# STM32.net
KiCad netlist of a schematic drawn in Altium Designer
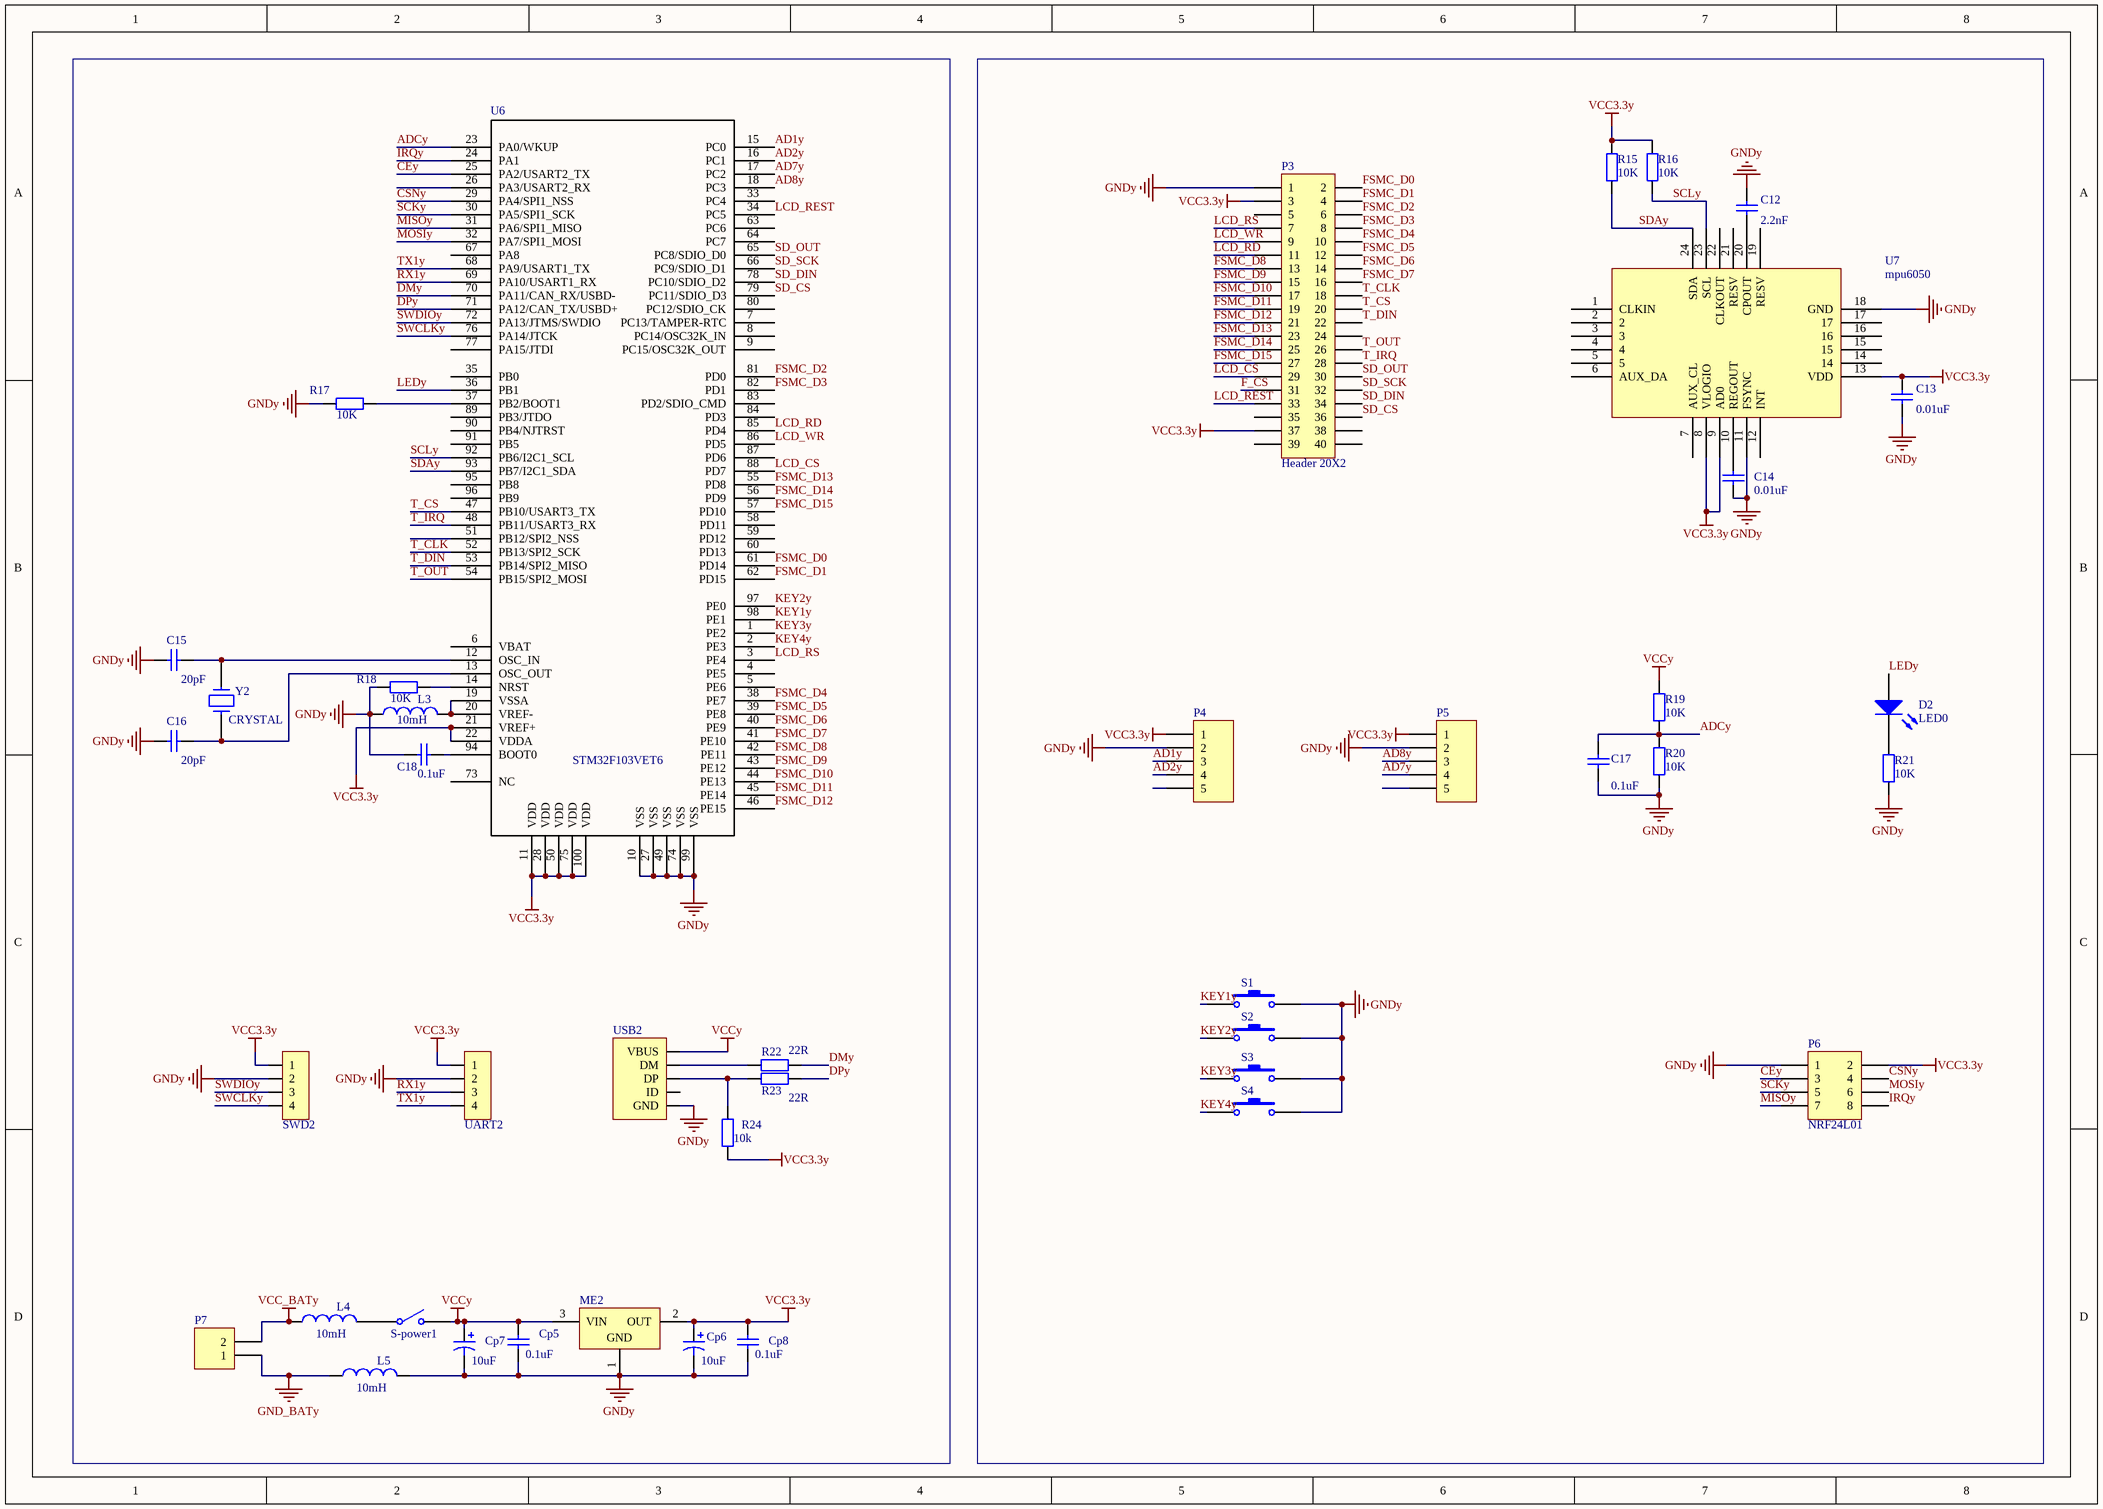
[diagram p0: STM32遥控.SchDoc]

(export (version "E")
  (design (tool "Eeschema 10.0.6"))
  (components
    (comp (ref "C12")
      (value "2.2nF")
      (footprint "0805s")
      (description "Capacitor")
      (fields (field (name "Comment") "Cap") (field (name "PUBLISHER") "Altium Limited"))
      (libsource (lib "Miscellaneous Devices") (part "Cap"))
    )
    (comp (ref "C13")
      (value "0.01uF")
      (footprint "0805s")
      (description "Capacitor")
      (fields (field (name "Comment") "Cap") (field (name "PUBLISHER") "Altium Limited"))
      (libsource (lib "Miscellaneous Devices") (part "Cap"))
    )
    (comp (ref "C14")
      (value "0.01uF")
      (footprint "0805s")
      (description "Capacitor")
      (fields (field (name "Comment") "Cap") (field (name "PUBLISHER") "Altium Limited"))
      (libsource (lib "Miscellaneous Devices") (part "Cap"))
    )
    (comp (ref "C15")
      (value "20pF")
      (footprint "0805s")
      (description "Capacitor")
      (fields (field (name "Comment") "Cap") (field (name "PUBLISHER") "Altium Limited"))
      (libsource (lib "Miscellaneous Devices") (part "Cap"))
    )
    (comp (ref "C16")
      (value "20pF")
      (footprint "0805s")
      (description "Capacitor")
      (fields (field (name "Comment") "Cap") (field (name "PUBLISHER") "Altium Limited"))
      (libsource (lib "Miscellaneous Devices") (part "Cap"))
    )
    (comp (ref "C17")
      (value "0.1uF")
      (footprint "0805s")
      (description "Capacitor")
      (fields (field (name "Comment") "Cap") (field (name "PUBLISHER") "Altium Limited"))
      (libsource (lib "Miscellaneous Devices") (part "Cap"))
    )
    (comp (ref "C18")
      (value "0.1uF")
      (footprint "0805s")
      (description "Capacitor")
      (fields (field (name "Comment") "Cap") (field (name "PUBLISHER") "Altium Limited"))
      (libsource (lib "Miscellaneous Devices") (part "Cap"))
    )
    (comp (ref "Cp5")
      (value "0.1uF")
      (footprint "0805s")
      (description "Capacitor")
      (fields (field (name "Comment") "Cap") (field (name "PUBLISHER") "Altium Limited"))
      (libsource (lib "Miscellaneous Devices") (part "Cap"))
    )
    (comp (ref "Cp6")
      (value "10uF")
      (footprint "3216")
      (description "Polarized Capacitor (Radial)")
      (fields (field (name "Comment") "Cap Pol1") (field (name "PUBLISHER") "Altium Limited"))
      (libsource (lib "Miscellaneous Devices") (part "Cap Pol1"))
    )
    (comp (ref "Cp7")
      (value "10uF")
      (footprint "3216")
      (description "Polarized Capacitor (Radial)")
      (fields (field (name "Comment") "Cap Pol1") (field (name "PUBLISHER") "Altium Limited"))
      (libsource (lib "Miscellaneous Devices") (part "Cap Pol1"))
    )
    (comp (ref "Cp8")
      (value "0.1uF")
      (footprint "0805s")
      (description "Capacitor")
      (fields (field (name "Comment") "Cap") (field (name "PUBLISHER") "Altium Limited"))
      (libsource (lib "Miscellaneous Devices") (part "Cap"))
    )
    (comp (ref "D2")
      (value "LED0")
      (footprint "0805s")
      (description "Typical INFRARED GaAs LED")
      (fields (field (name "PUBLISHER") "Altium Limited"))
      (libsource (lib "Miscellaneous Devices") (part "LED0"))
    )
    (comp (ref "L3")
      (value "10mH")
      (footprint "0805s")
      (description "Inductor")
      (fields (field (name "PUBLISHER") "Altium Limited"))
      (libsource (lib "Miscellaneous Devices") (part "Inductor"))
    )
    (comp (ref "L4")
      (value "10mH")
      (footprint "0805s")
      (description "Inductor")
      (fields (field (name "PUBLISHER") "Altium Limited"))
      (libsource (lib "Miscellaneous Devices") (part "Inductor"))
    )
    (comp (ref "L5")
      (value "10mH")
      (footprint "0805s")
      (description "Inductor")
      (fields (field (name "PUBLISHER") "Altium Limited"))
      (libsource (lib "Miscellaneous Devices") (part "Inductor"))
    )
    (comp (ref "ME2")
      (value "Volt Reg")
      (footprint "SOT-23")
      (description "Voltage Regulator")
      (fields (field (name "PUBLISHER") "Altium Limited"))
      (libsource (lib "Miscellaneous Devices") (part "Volt Reg"))
    )
    (comp (ref "P3")
      (value "Header 20X2")
      (footprint "HDR2X20")
      (description "Header, 20-Pin, Dual row")
      (fields (field (name "PUBLISHER") "Altium Limited"))
      (libsource (lib "Miscellaneous Connectors") (part "Header 20X2"))
    )
    (comp (ref "P4")
      (value "Header 5")
      (footprint "yaogan")
      (description "Header, 5-Pin")
      (fields (field (name "PUBLISHER") "Altium Limited"))
      (libsource (lib "Miscellaneous Connectors") (part "Header 5"))
    )
    (comp (ref "P5")
      (value "Header 5")
      (footprint "yaogan")
      (description "Header, 5-Pin")
      (fields (field (name "PUBLISHER") "Altium Limited"))
      (libsource (lib "Miscellaneous Connectors") (part "Header 5"))
    )
    (comp (ref "P6")
      (value "NRF24L01")
      (footprint "HDR2X4")
      (description "Header, 4-Pin, Dual row")
      (fields (field (name "PUBLISHER") "Altium Limited"))
      (libsource (lib "Miscellaneous Connectors") (part "MHDR2X4"))
    )
    (comp (ref "P7")
      (value "Header 2")
      (footprint "SIP2")
      (description "Header, 2-Pin")
      (fields (field (name "PUBLISHER") "Altium Limited"))
      (libsource (lib "Miscellaneous Connectors") (part "Header 2"))
    )
    (comp (ref "R15")
      (value "10K")
      (footprint "0805s")
      (description "Resistor")
      (fields (field (name "Comment") "Res2") (field (name "PUBLISHER") "Altium Limited"))
      (libsource (lib "Miscellaneous Devices") (part "Res2"))
    )
    (comp (ref "R16")
      (value "10K")
      (footprint "0805s")
      (description "Resistor")
      (fields (field (name "Comment") "Res2") (field (name "PUBLISHER") "Altium Limited"))
      (libsource (lib "Miscellaneous Devices") (part "Res2"))
    )
    (comp (ref "R17")
      (value "10K")
      (footprint "0805s")
      (description "Resistor")
      (fields (field (name "Comment") "Res2") (field (name "PUBLISHER") "Altium Limited"))
      (libsource (lib "") (part "Res2_1"))
    )
    (comp (ref "R18")
      (value "10K")
      (footprint "0805s")
      (description "Resistor")
      (fields (field (name "Comment") "Res2") (field (name "PUBLISHER") "Altium Limited"))
      (libsource (lib "") (part "Res2_1"))
    )
    (comp (ref "R19")
      (value "10K")
      (footprint "0805s")
      (description "Resistor")
      (fields (field (name "Comment") "Res2") (field (name "PUBLISHER") "Altium Limited"))
      (libsource (lib "Miscellaneous Devices") (part "Res2"))
    )
    (comp (ref "R20")
      (value "10K")
      (footprint "0805s")
      (description "Resistor")
      (fields (field (name "Comment") "Res2") (field (name "PUBLISHER") "Altium Limited"))
      (libsource (lib "Miscellaneous Devices") (part "Res2"))
    )
    (comp (ref "R21")
      (value "10K")
      (footprint "0805s")
      (description "Resistor")
      (fields (field (name "Comment") "Res2") (field (name "PUBLISHER") "Altium Limited"))
      (libsource (lib "Miscellaneous Devices") (part "Res2"))
    )
    (comp (ref "R22")
      (value "22R")
      (footprint "0805s")
      (description "Resistor")
      (fields (field (name "Comment") "Res_0603"))
      (libsource (lib "SCH_Passive") (part "Res_0603"))
    )
    (comp (ref "R23")
      (value "22R")
      (footprint "0805s")
      (description "Resistor")
      (fields (field (name "Comment") "Res_0603"))
      (libsource (lib "SCH_Passive") (part "Res_0603"))
    )
    (comp (ref "R24")
      (value "10k")
      (footprint "常用元件封装:0805s")
      (description "Resistor")
      (fields (field (name "Comment") "Res_0603"))
      (libsource (lib "") (part "Res_0603_1"))
    )
    (comp (ref "S-power1")
      (value "SW-SPST")
      (footprint "SIP3")
      (description "Single-Pole, Single-Throw Switch")
      (fields (field (name "PUBLISHER") "Altium Limited"))
      (libsource (lib "Miscellaneous Devices") (part "SW-SPST"))
    )
    (comp (ref "S1")
      (value "SW-PB")
      (footprint "按键")
      (description "Switch")
      (fields (field (name "PUBLISHER") "Altium Limited"))
      (libsource (lib "Miscellaneous Devices") (part "SW-PB"))
    )
    (comp (ref "S2")
      (value "SW-PB")
      (footprint "按键")
      (description "Switch")
      (fields (field (name "PUBLISHER") "Altium Limited"))
      (libsource (lib "Miscellaneous Devices") (part "SW-PB"))
    )
    (comp (ref "S3")
      (value "SW-PB")
      (footprint "按键")
      (description "Switch")
      (fields (field (name "PUBLISHER") "Altium Limited"))
      (libsource (lib "Miscellaneous Devices") (part "SW-PB"))
    )
    (comp (ref "S4")
      (value "SW-PB")
      (footprint "按键")
      (description "Switch")
      (fields (field (name "PUBLISHER") "Altium Limited"))
      (libsource (lib "Miscellaneous Devices") (part "SW-PB"))
    )
    (comp (ref "SWD2")
      (value "HDR1X4_180_2.54")
      (footprint "SIP4")
      (description "Header")
      (libsource (lib "SCH_Connector") (part "HDR1X4_180_2.54"))
    )
    (comp (ref "U6")
      (value "STM32F103VET6")
      (footprint "LQFP100_N")
      (libsource (lib "Schlib1") (part "STM32F103VET6"))
    )
    (comp (ref "U7") (value "mpu6050") (footprint "MPU6050") (libsource (lib "四轴") (part "mpu6050")))
    (comp (ref "UART2")
      (value "HDR1X4_180_2.54")
      (footprint "SIP4")
      (description "Header")
      (libsource (lib "SCH_Connector") (part "HDR1X4_180_2.54"))
    )
    (comp (ref "USB2")
      (value "USB_Micro")
      (footprint "MICRO-USB")
      (description "USB")
      (libsource (lib "SCH_USB") (part "USB_Micro"))
    )
    (comp (ref "Y2")
      (value "CRYSTAL")
      (footprint "SIP2")
      (description "Crystal")
      (libsource (lib "杂元件库") (part "CRYSTAL"))
    )
  )
  (nets
    (net (code "1") (name "/AD1y") (class "Default")
      (node (ref "P4") (pin "3") (pinfunction "3_3") (pintype "passive"))
      (node (ref "U6") (pin "15") (pinfunction "PC0_15") (pintype "passive"))
    )
    (net (code "2") (name "/AD2y") (class "Default")
      (node (ref "P4") (pin "4") (pinfunction "4_4") (pintype "passive"))
      (node (ref "U6") (pin "16") (pinfunction "PC1_16") (pintype "passive"))
    )
    (net (code "3") (name "/AD7y") (class "Default")
      (node (ref "P5") (pin "4") (pinfunction "4_4") (pintype "passive"))
      (node (ref "U6") (pin "17") (pinfunction "PC2_17") (pintype "passive"))
    )
    (net (code "4") (name "/AD8y") (class "Default")
      (node (ref "P5") (pin "3") (pinfunction "3_3") (pintype "passive"))
      (node (ref "U6") (pin "18") (pinfunction "PC3_18") (pintype "passive"))
    )
    (net (code "5") (name "/ADCy") (class "Default")
      (node (ref "C17") (pin "2") (pinfunction "2_2") (pintype "passive"))
      (node (ref "R19") (pin "1") (pinfunction "1_1") (pintype "passive"))
      (node (ref "R20") (pin "2") (pinfunction "2_2") (pintype "passive"))
      (node (ref "U6") (pin "23") (pinfunction "PA0/WKUP_23") (pintype "passive"))
    )
    (net (code "6") (name "/CEy") (class "Default")
      (node (ref "P6") (pin "3") (pinfunction "3_3") (pintype "passive"))
      (node (ref "U6") (pin "25") (pinfunction "PA2/USART2_TX_25") (pintype "passive"))
    )
    (net (code "7") (name "/CSNy") (class "Default")
      (node (ref "P6") (pin "4") (pinfunction "4_4") (pintype "passive"))
      (node (ref "U6") (pin "29") (pinfunction "PA4/SPI1_NSS_29") (pintype "passive"))
    )
    (net (code "8") (name "/DMy") (class "Default")
      (node (ref "R22") (pin "2") (pinfunction "2_2") (pintype "passive"))
      (node (ref "U6") (pin "70") (pinfunction "PA11/CAN_RX/USBD-_70") (pintype "passive"))
    )
    (net (code "9") (name "/DPy") (class "Default")
      (node (ref "R23") (pin "2") (pinfunction "2_2") (pintype "passive"))
      (node (ref "U6") (pin "71") (pinfunction "PA12/CAN_TX/USBD+_71") (pintype "passive"))
    )
    (net (code "10") (name "/FSMC_D0") (class "Default")
      (node (ref "P3") (pin "2") (pinfunction "2_2") (pintype "passive"))
      (node (ref "U6") (pin "61") (pinfunction "PD14_61") (pintype "passive"))
    )
    (net (code "11") (name "/FSMC_D1") (class "Default")
      (node (ref "P3") (pin "4") (pinfunction "4_4") (pintype "passive"))
      (node (ref "U6") (pin "62") (pinfunction "PD15_62") (pintype "passive"))
    )
    (net (code "12") (name "/FSMC_D2") (class "Default")
      (node (ref "P3") (pin "6") (pinfunction "6_6") (pintype "passive"))
      (node (ref "U6") (pin "81") (pinfunction "PD0_81") (pintype "passive"))
    )
    (net (code "13") (name "/FSMC_D3") (class "Default")
      (node (ref "P3") (pin "8") (pinfunction "8_8") (pintype "passive"))
      (node (ref "U6") (pin "82") (pinfunction "PD1_82") (pintype "passive"))
    )
    (net (code "14") (name "/FSMC_D4") (class "Default")
      (node (ref "P3") (pin "10") (pinfunction "10_10") (pintype "passive"))
      (node (ref "U6") (pin "38") (pinfunction "PE7_38") (pintype "passive"))
    )
    (net (code "15") (name "/FSMC_D5") (class "Default")
      (node (ref "P3") (pin "12") (pinfunction "12_12") (pintype "passive"))
      (node (ref "U6") (pin "39") (pinfunction "PE8_39") (pintype "passive"))
    )
    (net (code "16") (name "/FSMC_D6") (class "Default")
      (node (ref "P3") (pin "14") (pinfunction "14_14") (pintype "passive"))
      (node (ref "U6") (pin "40") (pinfunction "PE9_40") (pintype "passive"))
    )
    (net (code "17") (name "/FSMC_D7") (class "Default")
      (node (ref "P3") (pin "16") (pinfunction "16_16") (pintype "passive"))
      (node (ref "U6") (pin "41") (pinfunction "PE10_41") (pintype "passive"))
    )
    (net (code "18") (name "/FSMC_D8") (class "Default")
      (node (ref "P3") (pin "13") (pinfunction "13_13") (pintype "passive"))
      (node (ref "U6") (pin "42") (pinfunction "PE11_42") (pintype "passive"))
    )
    (net (code "19") (name "/FSMC_D9") (class "Default")
      (node (ref "P3") (pin "15") (pinfunction "15_15") (pintype "passive"))
      (node (ref "U6") (pin "43") (pinfunction "PE12_43") (pintype "passive"))
    )
    (net (code "20") (name "/FSMC_D10") (class "Default")
      (node (ref "P3") (pin "17") (pinfunction "17_17") (pintype "passive"))
      (node (ref "U6") (pin "44") (pinfunction "PE13_44") (pintype "passive"))
    )
    (net (code "21") (name "/FSMC_D11") (class "Default")
      (node (ref "P3") (pin "19") (pinfunction "19_19") (pintype "passive"))
      (node (ref "U6") (pin "45") (pinfunction "PE14_45") (pintype "passive"))
    )
    (net (code "22") (name "/FSMC_D12") (class "Default")
      (node (ref "P3") (pin "21") (pinfunction "21_21") (pintype "passive"))
      (node (ref "U6") (pin "46") (pinfunction "PE15_46") (pintype "passive"))
    )
    (net (code "23") (name "/FSMC_D13") (class "Default")
      (node (ref "P3") (pin "23") (pinfunction "23_23") (pintype "passive"))
      (node (ref "U6") (pin "55") (pinfunction "PD8_55") (pintype "passive"))
    )
    (net (code "24") (name "/FSMC_D14") (class "Default")
      (node (ref "P3") (pin "25") (pinfunction "25_25") (pintype "passive"))
      (node (ref "U6") (pin "56") (pinfunction "PD9_56") (pintype "passive"))
    )
    (net (code "25") (name "/FSMC_D15") (class "Default")
      (node (ref "P3") (pin "27") (pinfunction "27_27") (pintype "passive"))
      (node (ref "U6") (pin "57") (pinfunction "PD10_57") (pintype "passive"))
    )
    (net (code "26") (name "/F_CS") (class "Default")
      (node (ref "P3") (pin "31") (pinfunction "31_31") (pintype "passive"))
    )
    (net (code "27") (name "/IRQy") (class "Default")
      (node (ref "P6") (pin "8") (pinfunction "8_8") (pintype "passive"))
      (node (ref "U6") (pin "24") (pinfunction "PA1_24") (pintype "passive"))
    )
    (net (code "28") (name "/KEY1y") (class "Default")
      (node (ref "S1") (pin "1") (pinfunction "1_1") (pintype "passive"))
      (node (ref "U6") (pin "98") (pinfunction "PE1_98") (pintype "passive"))
    )
    (net (code "29") (name "/KEY2y") (class "Default")
      (node (ref "S2") (pin "1") (pinfunction "1_1") (pintype "passive"))
      (node (ref "U6") (pin "97") (pinfunction "PE0_97") (pintype "passive"))
    )
    (net (code "30") (name "/KEY3y") (class "Default")
      (node (ref "S3") (pin "1") (pinfunction "1_1") (pintype "passive"))
      (node (ref "U6") (pin "1") (pinfunction "PE2_1") (pintype "passive"))
    )
    (net (code "31") (name "/KEY4y") (class "Default")
      (node (ref "S4") (pin "1") (pinfunction "1_1") (pintype "passive"))
      (node (ref "U6") (pin "2") (pinfunction "PE3_2") (pintype "passive"))
    )
    (net (code "32") (name "/LCD_CS") (class "Default")
      (node (ref "P3") (pin "29") (pinfunction "29_29") (pintype "passive"))
      (node (ref "U6") (pin "88") (pinfunction "PD7_88") (pintype "passive"))
    )
    (net (code "33") (name "/LCD_RD") (class "Default")
      (node (ref "P3") (pin "11") (pinfunction "11_11") (pintype "passive"))
      (node (ref "U6") (pin "85") (pinfunction "PD4_85") (pintype "passive"))
    )
    (net (code "34") (name "/LCD_REST") (class "Default")
      (node (ref "P3") (pin "33") (pinfunction "33_33") (pintype "passive"))
      (node (ref "U6") (pin "34") (pinfunction "PC5_34") (pintype "passive"))
    )
    (net (code "35") (name "/LCD_RS") (class "Default")
      (node (ref "P3") (pin "7") (pinfunction "7_7") (pintype "passive"))
      (node (ref "U6") (pin "3") (pinfunction "PE4_3") (pintype "passive"))
    )
    (net (code "36") (name "/LCD_WR") (class "Default")
      (node (ref "P3") (pin "9") (pinfunction "9_9") (pintype "passive"))
      (node (ref "U6") (pin "86") (pinfunction "PD5_86") (pintype "passive"))
    )
    (net (code "37") (name "/LEDy") (class "Default")
      (node (ref "D2") (pin "1") (pinfunction "A_1") (pintype "passive"))
      (node (ref "U6") (pin "36") (pinfunction "PB1_36") (pintype "passive"))
    )
    (net (code "38") (name "/MISOy") (class "Default")
      (node (ref "P6") (pin "7") (pinfunction "7_7") (pintype "passive"))
      (node (ref "U6") (pin "31") (pinfunction "PA6/SPI1_MISO_31") (pintype "passive"))
    )
    (net (code "39") (name "/MOSIy") (class "Default")
      (node (ref "P6") (pin "6") (pinfunction "6_6") (pintype "passive"))
      (node (ref "U6") (pin "32") (pinfunction "PA7/SPI1_MOSI_32") (pintype "passive"))
    )
    (net (code "40") (name "/RX1y") (class "Default")
      (node (ref "U6") (pin "69") (pinfunction "PA10/USART1_RX_69") (pintype "passive"))
      (node (ref "UART2") (pin "3") (pinfunction "3_3") (pintype "passive"))
    )
    (net (code "41") (name "/SCKy") (class "Default")
      (node (ref "P6") (pin "5") (pinfunction "5_5") (pintype "passive"))
      (node (ref "U6") (pin "30") (pinfunction "PA5/SPI1_SCK_30") (pintype "passive"))
    )
    (net (code "42") (name "/SCLy") (class "Default")
      (node (ref "R16") (pin "1") (pinfunction "1_1") (pintype "passive"))
      (node (ref "U6") (pin "92") (pinfunction "PB6/I2C1_SCL_92") (pintype "passive"))
      (node (ref "U7") (pin "23") (pinfunction "SCL_23") (pintype "passive"))
    )
    (net (code "43") (name "/SDAy") (class "Default")
      (node (ref "R15") (pin "1") (pinfunction "1_1") (pintype "passive"))
      (node (ref "U6") (pin "93") (pinfunction "PB7/I2C1_SDA_93") (pintype "passive"))
      (node (ref "U7") (pin "24") (pinfunction "SDA_24") (pintype "passive"))
    )
    (net (code "44") (name "/SD_CS") (class "Default")
      (node (ref "P3") (pin "36") (pinfunction "36_36") (pintype "passive"))
      (node (ref "U6") (pin "79") (pinfunction "PC11/SDIO_D3_79") (pintype "passive"))
    )
    (net (code "45") (name "/SD_DIN") (class "Default")
      (node (ref "P3") (pin "34") (pinfunction "34_34") (pintype "passive"))
      (node (ref "U6") (pin "78") (pinfunction "PC10/SDIO_D2_78") (pintype "passive"))
    )
    (net (code "46") (name "/SD_OUT") (class "Default")
      (node (ref "P3") (pin "30") (pinfunction "30_30") (pintype "passive"))
      (node (ref "U6") (pin "65") (pinfunction "PC8/SDIO_D0_65") (pintype "passive"))
    )
    (net (code "47") (name "/SD_SCK") (class "Default")
      (node (ref "P3") (pin "32") (pinfunction "32_32") (pintype "passive"))
      (node (ref "U6") (pin "66") (pinfunction "PC9/SDIO_D1_66") (pintype "passive"))
    )
    (net (code "48") (name "/SWCLKy") (class "Default")
      (node (ref "SWD2") (pin "4") (pinfunction "4_4") (pintype "passive"))
      (node (ref "U6") (pin "76") (pinfunction "PA14/JTCK_76") (pintype "passive"))
    )
    (net (code "49") (name "/SWDIOy") (class "Default")
      (node (ref "SWD2") (pin "3") (pinfunction "3_3") (pintype "passive"))
      (node (ref "U6") (pin "72") (pinfunction "PA13/JTMS/SWDIO_72") (pintype "passive"))
    )
    (net (code "50") (name "/TX1y") (class "Default")
      (node (ref "U6") (pin "68") (pinfunction "PA9/USART1_TX_68") (pintype "passive"))
      (node (ref "UART2") (pin "4") (pinfunction "4_4") (pintype "passive"))
    )
    (net (code "51") (name "/T_CLK") (class "Default")
      (node (ref "P3") (pin "18") (pinfunction "18_18") (pintype "passive"))
      (node (ref "U6") (pin "52") (pinfunction "PB13/SPI2_SCK_52") (pintype "passive"))
    )
    (net (code "52") (name "/T_CS") (class "Default")
      (node (ref "P3") (pin "20") (pinfunction "20_20") (pintype "passive"))
      (node (ref "U6") (pin "47") (pinfunction "PB10/USART3_TX_47") (pintype "passive"))
    )
    (net (code "53") (name "/T_DIN") (class "Default")
      (node (ref "P3") (pin "22") (pinfunction "22_22") (pintype "passive"))
      (node (ref "U6") (pin "53") (pinfunction "PB14/SPI2_MISO_53") (pintype "passive"))
    )
    (net (code "54") (name "/T_IRQ") (class "Default")
      (node (ref "P3") (pin "28") (pinfunction "28_28") (pintype "passive"))
      (node (ref "U6") (pin "48") (pinfunction "PB11/USART3_RX_48") (pintype "passive"))
    )
    (net (code "55") (name "/T_OUT") (class "Default")
      (node (ref "P3") (pin "26") (pinfunction "26_26") (pintype "passive"))
      (node (ref "U6") (pin "54") (pinfunction "PB15/SPI2_MOSI_54") (pintype "passive"))
    )
    (net (code "56") (name "GND_BATy") (class "Default")
      (node (ref "L5") (pin "1") (pinfunction "1_1") (pintype "passive"))
      (node (ref "P7") (pin "1") (pinfunction "1_1") (pintype "passive"))
    )
    (net (code "57") (name "GNDy") (class "Default")
      (node (ref "C12") (pin "2") (pinfunction "2_2") (pintype "passive"))
      (node (ref "C13") (pin "1") (pinfunction "1_1") (pintype "passive"))
      (node (ref "C14") (pin "1") (pinfunction "1_1") (pintype "passive"))
      (node (ref "C15") (pin "1") (pinfunction "1_1") (pintype "passive"))
      (node (ref "C16") (pin "1") (pinfunction "1_1") (pintype "passive"))
      (node (ref "C17") (pin "1") (pinfunction "1_1") (pintype "passive"))
      (node (ref "C18") (pin "1") (pinfunction "1_1") (pintype "passive"))
      (node (ref "Cp5") (pin "1") (pinfunction "1_1") (pintype "passive"))
      (node (ref "Cp6") (pin "2") (pinfunction "2_2") (pintype "passive"))
      (node (ref "Cp7") (pin "2") (pinfunction "2_2") (pintype "passive"))
      (node (ref "Cp8") (pin "1") (pinfunction "1_1") (pintype "passive"))
      (node (ref "L3") (pin "1") (pinfunction "1_1") (pintype "passive"))
      (node (ref "L5") (pin "2") (pinfunction "2_2") (pintype "passive"))
      (node (ref "ME2") (pin "1") (pinfunction "GND_1") (pintype "passive"))
      (node (ref "P3") (pin "1") (pinfunction "1_1") (pintype "passive"))
      (node (ref "P4") (pin "2") (pinfunction "2_2") (pintype "passive"))
      (node (ref "P5") (pin "2") (pinfunction "2_2") (pintype "passive"))
      (node (ref "P6") (pin "1") (pinfunction "1_1") (pintype "passive"))
      (node (ref "R17") (pin "2") (pinfunction "2_2") (pintype "passive"))
      (node (ref "R18") (pin "2") (pinfunction "2_2") (pintype "passive"))
      (node (ref "R20") (pin "1") (pinfunction "1_1") (pintype "passive"))
      (node (ref "R21") (pin "1") (pinfunction "1_1") (pintype "passive"))
      (node (ref "S1") (pin "2") (pinfunction "2_2") (pintype "passive"))
      (node (ref "S2") (pin "2") (pinfunction "2_2") (pintype "passive"))
      (node (ref "S3") (pin "2") (pinfunction "2_2") (pintype "passive"))
      (node (ref "S4") (pin "2") (pinfunction "2_2") (pintype "passive"))
      (node (ref "SWD2") (pin "2") (pinfunction "2_2") (pintype "passive"))
      (node (ref "U6") (pin "10") (pinfunction "VSS_10") (pintype "passive"))
      (node (ref "U6") (pin "27") (pinfunction "VSS_27") (pintype "passive"))
      (node (ref "U6") (pin "49") (pinfunction "VSS_49") (pintype "passive"))
      (node (ref "U6") (pin "74") (pinfunction "VSS_74") (pintype "passive"))
      (node (ref "U6") (pin "99") (pinfunction "VSS_99") (pintype "passive"))
      (node (ref "U7") (pin "11") (pinfunction "FSYNC_11") (pintype "passive"))
      (node (ref "U7") (pin "18") (pinfunction "GND_18") (pintype "passive"))
      (node (ref "UART2") (pin "2") (pinfunction "2_2") (pintype "passive"))
      (node (ref "USB2") (pin "5") (pinfunction "GND_5") (pintype "passive"))
    )
    (net (code "58") (name "Net-(D2-K)") (class "Default")
      (node (ref "D2") (pin "2") (pinfunction "K_2") (pintype "passive"))
      (node (ref "R21") (pin "2") (pinfunction "2_2") (pintype "passive"))
    )
    (net (code "59") (name "Net-(S-power1-COMMON)") (class "Default")
      (node (ref "L4") (pin "2") (pinfunction "2_2") (pintype "passive"))
      (node (ref "S-power1") (pin "1") (pinfunction "COMMON_1") (pintype "passive"))
    )
    (net (code "60") (name "Net-(U6-BOOT0)") (class "Default")
      (node (ref "C18") (pin "2") (pinfunction "2_2") (pintype "passive"))
      (node (ref "U6") (pin "94") (pinfunction "BOOT0_94") (pintype "passive"))
    )
    (net (code "61") (name "Net-(U6-NRST)") (class "Default")
      (node (ref "R18") (pin "1") (pinfunction "1_1") (pintype "passive"))
      (node (ref "U6") (pin "14") (pinfunction "NRST_14") (pintype "passive"))
    )
    (net (code "62") (name "Net-(U6-OSC_IN)") (class "Default")
      (node (ref "C15") (pin "2") (pinfunction "2_2") (pintype "passive"))
      (node (ref "U6") (pin "12") (pinfunction "OSC_IN_12") (pintype "passive"))
      (node (ref "Y2") (pin "2") (pinfunction "2_2") (pintype "passive"))
    )
    (net (code "63") (name "Net-(U6-OSC_OUT)") (class "Default")
      (node (ref "C16") (pin "2") (pinfunction "2_2") (pintype "passive"))
      (node (ref "U6") (pin "13") (pinfunction "OSC_OUT_13") (pintype "passive"))
      (node (ref "Y2") (pin "1") (pinfunction "1_1") (pintype "passive"))
    )
    (net (code "64") (name "Net-(U6-PB2{slash}BOOT1)") (class "Default")
      (node (ref "R17") (pin "1") (pinfunction "1_1") (pintype "passive"))
      (node (ref "U6") (pin "37") (pinfunction "PB2/BOOT1_37") (pintype "passive"))
    )
    (net (code "65") (name "Net-(U6-VREF-)") (class "Default")
      (node (ref "L3") (pin "2") (pinfunction "2_2") (pintype "passive"))
      (node (ref "U6") (pin "19") (pinfunction "VSSA_19") (pintype "passive"))
      (node (ref "U6") (pin "20") (pinfunction "VREF-_20") (pintype "passive"))
    )
    (net (code "66") (name "Net-(U7-CPOUT)") (class "Default")
      (node (ref "C12") (pin "1") (pinfunction "1_1") (pintype "passive"))
      (node (ref "U7") (pin "20") (pinfunction "CPOUT_20") (pintype "passive"))
    )
    (net (code "67") (name "Net-(U7-REGOUT)") (class "Default")
      (node (ref "C14") (pin "2") (pinfunction "2_2") (pintype "passive"))
      (node (ref "U7") (pin "10") (pinfunction "REGOUT_10") (pintype "passive"))
    )
    (net (code "68") (name "Net-(USB2-DM)") (class "Default")
      (node (ref "R22") (pin "1") (pinfunction "1_1") (pintype "passive"))
      (node (ref "USB2") (pin "2") (pinfunction "DM_2") (pintype "passive"))
    )
    (net (code "69") (name "Net-(USB2-DP)") (class "Default")
      (node (ref "R23") (pin "1") (pinfunction "1_1") (pintype "passive"))
      (node (ref "R24") (pin "1") (pinfunction "1_1") (pintype "passive"))
      (node (ref "USB2") (pin "3") (pinfunction "DP_3") (pintype "passive"))
    )
    (net (code "70") (name "VCC3.3y") (class "Default")
      (node (ref "C13") (pin "2") (pinfunction "2_2") (pintype "passive"))
      (node (ref "Cp6") (pin "1") (pinfunction "1_1") (pintype "passive"))
      (node (ref "Cp8") (pin "2") (pinfunction "2_2") (pintype "passive"))
      (node (ref "ME2") (pin "2") (pinfunction "OUT_2") (pintype "passive"))
      (node (ref "P3") (pin "3") (pinfunction "3_3") (pintype "passive"))
      (node (ref "P3") (pin "37") (pinfunction "37_37") (pintype "passive"))
      (node (ref "P4") (pin "1") (pinfunction "1_1") (pintype "passive"))
      (node (ref "P5") (pin "1") (pinfunction "1_1") (pintype "passive"))
      (node (ref "P6") (pin "2") (pinfunction "2_2") (pintype "passive"))
      (node (ref "R15") (pin "2") (pinfunction "2_2") (pintype "passive"))
      (node (ref "R16") (pin "2") (pinfunction "2_2") (pintype "passive"))
      (node (ref "R24") (pin "2") (pinfunction "2_2") (pintype "passive"))
      (node (ref "SWD2") (pin "1") (pinfunction "1_1") (pintype "passive"))
      (node (ref "U6") (pin "100") (pinfunction "VDD_100") (pintype "passive"))
      (node (ref "U6") (pin "11") (pinfunction "VDD_11") (pintype "passive"))
      (node (ref "U6") (pin "21") (pinfunction "VREF+_21") (pintype "passive"))
      (node (ref "U6") (pin "22") (pinfunction "VDDA_22") (pintype "passive"))
      (node (ref "U6") (pin "28") (pinfunction "VDD_28") (pintype "passive"))
      (node (ref "U6") (pin "50") (pinfunction "VDD_50") (pintype "passive"))
      (node (ref "U6") (pin "75") (pinfunction "VDD_75") (pintype "passive"))
      (node (ref "U7") (pin "13") (pinfunction "VDD_13") (pintype "passive"))
      (node (ref "U7") (pin "8") (pinfunction "VLOGIO_8") (pintype "passive"))
      (node (ref "U7") (pin "9") (pinfunction "AD0_9") (pintype "passive"))
      (node (ref "UART2") (pin "1") (pinfunction "1_1") (pintype "passive"))
    )
    (net (code "71") (name "VCC_BATy") (class "Default")
      (node (ref "L4") (pin "1") (pinfunction "1_1") (pintype "passive"))
      (node (ref "P7") (pin "2") (pinfunction "2_2") (pintype "passive"))
    )
    (net (code "72") (name "VCCy") (class "Default")
      (node (ref "Cp5") (pin "2") (pinfunction "2_2") (pintype "passive"))
      (node (ref "Cp7") (pin "1") (pinfunction "1_1") (pintype "passive"))
      (node (ref "ME2") (pin "3") (pinfunction "VIN_3") (pintype "passive"))
      (node (ref "R19") (pin "2") (pinfunction "2_2") (pintype "passive"))
      (node (ref "S-power1") (pin "2") (pinfunction "NO_2") (pintype "passive"))
      (node (ref "USB2") (pin "1") (pinfunction "VBUS_1") (pintype "passive"))
    )
    (net (code "73") (name "unconnected-(P3-Pad5)") (class "Default")
      (node (ref "P3") (pin "5") (pinfunction "5_5") (pintype "passive"))
    )
    (net (code "74") (name "unconnected-(P3-Pad24)") (class "Default")
      (node (ref "P3") (pin "24") (pinfunction "24_24") (pintype "passive"))
    )
    (net (code "75") (name "unconnected-(P3-Pad35)") (class "Default")
      (node (ref "P3") (pin "35") (pinfunction "35_35") (pintype "passive"))
    )
    (net (code "76") (name "unconnected-(P3-Pad38)") (class "Default")
      (node (ref "P3") (pin "38") (pinfunction "38_38") (pintype "passive"))
    )
    (net (code "77") (name "unconnected-(P3-Pad39)") (class "Default")
      (node (ref "P3") (pin "39") (pinfunction "39_39") (pintype "passive"))
    )
    (net (code "78") (name "unconnected-(P3-Pad40)") (class "Default")
      (node (ref "P3") (pin "40") (pinfunction "40_40") (pintype "passive"))
    )
    (net (code "79") (name "unconnected-(P4-Pad5)") (class "Default")
      (node (ref "P4") (pin "5") (pinfunction "5_5") (pintype "passive"))
    )
    (net (code "80") (name "unconnected-(P5-Pad5)") (class "Default")
      (node (ref "P5") (pin "5") (pinfunction "5_5") (pintype "passive"))
    )
    (net (code "81") (name "unconnected-(U6-NC-Pad73)") (class "Default")
      (node (ref "U6") (pin "73") (pinfunction "NC_73") (pintype "passive"))
    )
    (net (code "82") (name "unconnected-(U6-PA3{slash}USART2_RX-Pad26)") (class "Default")
      (node (ref "U6") (pin "26") (pinfunction "PA3/USART2_RX_26") (pintype "passive"))
    )
    (net (code "83") (name "unconnected-(U6-PA8-Pad67)") (class "Default")
      (node (ref "U6") (pin "67") (pinfunction "PA8_67") (pintype "passive"))
    )
    (net (code "84") (name "unconnected-(U6-PA15{slash}JTDI-Pad77)") (class "Default")
      (node (ref "U6") (pin "77") (pinfunction "PA15/JTDI_77") (pintype "passive"))
    )
    (net (code "85") (name "unconnected-(U6-PB0-Pad35)") (class "Default")
      (node (ref "U6") (pin "35") (pinfunction "PB0_35") (pintype "passive"))
    )
    (net (code "86") (name "unconnected-(U6-PB3{slash}JTDO-Pad89)") (class "Default")
      (node (ref "U6") (pin "89") (pinfunction "PB3/JTDO_89") (pintype "passive"))
    )
    (net (code "87") (name "unconnected-(U6-PB4{slash}NJTRST-Pad90)") (class "Default")
      (node (ref "U6") (pin "90") (pinfunction "PB4/NJTRST_90") (pintype "passive"))
    )
    (net (code "88") (name "unconnected-(U6-PB5-Pad91)") (class "Default")
      (node (ref "U6") (pin "91") (pinfunction "PB5_91") (pintype "passive"))
    )
    (net (code "89") (name "unconnected-(U6-PB8-Pad95)") (class "Default")
      (node (ref "U6") (pin "95") (pinfunction "PB8_95") (pintype "passive"))
    )
    (net (code "90") (name "unconnected-(U6-PB9-Pad96)") (class "Default")
      (node (ref "U6") (pin "96") (pinfunction "PB9_96") (pintype "passive"))
    )
    (net (code "91") (name "unconnected-(U6-PB12{slash}SPI2_NSS-Pad51)") (class "Default")
      (node (ref "U6") (pin "51") (pinfunction "PB12/SPI2_NSS_51") (pintype "passive"))
    )
    (net (code "92") (name "unconnected-(U6-PC4-Pad33)") (class "Default")
      (node (ref "U6") (pin "33") (pinfunction "PC4_33") (pintype "passive"))
    )
    (net (code "93") (name "unconnected-(U6-PC6-Pad63)") (class "Default")
      (node (ref "U6") (pin "63") (pinfunction "PC6_63") (pintype "passive"))
    )
    (net (code "94") (name "unconnected-(U6-PC7-Pad64)") (class "Default")
      (node (ref "U6") (pin "64") (pinfunction "PC7_64") (pintype "passive"))
    )
    (net (code "95") (name "unconnected-(U6-PC12{slash}SDIO_CK-Pad80)") (class "Default")
      (node (ref "U6") (pin "80") (pinfunction "PC12/SDIO_CK_80") (pintype "passive"))
    )
    (net (code "96") (name "unconnected-(U6-PC13{slash}TAMPER-RTC-Pad7)") (class "Default")
      (node (ref "U6") (pin "7") (pinfunction "PC13/TAMPER-RTC_7") (pintype "passive"))
    )
    (net (code "97") (name "unconnected-(U6-PC14{slash}OSC32K_IN-Pad8)") (class "Default")
      (node (ref "U6") (pin "8") (pinfunction "PC14/OSC32K_IN_8") (pintype "passive"))
    )
    (net (code "98") (name "unconnected-(U6-PC15{slash}OSC32K_OUT-Pad9)") (class "Default")
      (node (ref "U6") (pin "9") (pinfunction "PC15/OSC32K_OUT_9") (pintype "passive"))
    )
    (net (code "99") (name "unconnected-(U6-PD2{slash}SDIO_CMD-Pad83)") (class "Default")
      (node (ref "U6") (pin "83") (pinfunction "PD2/SDIO_CMD_83") (pintype "passive"))
    )
    (net (code "100") (name "unconnected-(U6-PD3-Pad84)") (class "Default")
      (node (ref "U6") (pin "84") (pinfunction "PD3_84") (pintype "passive"))
    )
    (net (code "101") (name "unconnected-(U6-PD6-Pad87)") (class "Default")
      (node (ref "U6") (pin "87") (pinfunction "PD6_87") (pintype "passive"))
    )
    (net (code "102") (name "unconnected-(U6-PD11-Pad58)") (class "Default")
      (node (ref "U6") (pin "58") (pinfunction "PD11_58") (pintype "passive"))
    )
    (net (code "103") (name "unconnected-(U6-PD12-Pad59)") (class "Default")
      (node (ref "U6") (pin "59") (pinfunction "PD12_59") (pintype "passive"))
    )
    (net (code "104") (name "unconnected-(U6-PD13-Pad60)") (class "Default")
      (node (ref "U6") (pin "60") (pinfunction "PD13_60") (pintype "passive"))
    )
    (net (code "105") (name "unconnected-(U6-PE5-Pad4)") (class "Default")
      (node (ref "U6") (pin "4") (pinfunction "PE5_4") (pintype "passive"))
    )
    (net (code "106") (name "unconnected-(U6-PE6-Pad5)") (class "Default")
      (node (ref "U6") (pin "5") (pinfunction "PE6_5") (pintype "passive"))
    )
    (net (code "107") (name "unconnected-(U6-VBAT-Pad6)") (class "Default")
      (node (ref "U6") (pin "6") (pinfunction "VBAT_6") (pintype "passive"))
    )
    (net (code "108") (name "unconnected-(U7-AUX_CL-Pad7)") (class "Default")
      (node (ref "U7") (pin "7") (pinfunction "AUX_CL_7") (pintype "passive"))
    )
    (net (code "109") (name "unconnected-(U7-AUX_DA-Pad6)") (class "Default")
      (node (ref "U7") (pin "6") (pinfunction "AUX_DA_6") (pintype "passive"))
    )
    (net (code "110") (name "unconnected-(U7-CLKIN-Pad1)") (class "Default")
      (node (ref "U7") (pin "1") (pinfunction "CLKIN_1") (pintype "passive"))
    )
    (net (code "111") (name "unconnected-(U7-CLKOUT-Pad22)") (class "Default")
      (node (ref "U7") (pin "22") (pinfunction "CLKOUT_22") (pintype "passive"))
    )
    (net (code "112") (name "unconnected-(U7-INT-Pad12)") (class "Default")
      (node (ref "U7") (pin "12") (pinfunction "INT_12") (pintype "passive"))
    )
    (net (code "113") (name "unconnected-(U7-Pad2)") (class "Default")
      (node (ref "U7") (pin "2") (pinfunction "2_2") (pintype "passive"))
    )
    (net (code "114") (name "unconnected-(U7-Pad3)") (class "Default")
      (node (ref "U7") (pin "3") (pinfunction "3_3") (pintype "passive"))
    )
    (net (code "115") (name "unconnected-(U7-Pad4)") (class "Default")
      (node (ref "U7") (pin "4") (pinfunction "4_4") (pintype "passive"))
    )
    (net (code "116") (name "unconnected-(U7-Pad5)") (class "Default")
      (node (ref "U7") (pin "5") (pinfunction "5_5") (pintype "passive"))
    )
    (net (code "117") (name "unconnected-(U7-Pad14)") (class "Default")
      (node (ref "U7") (pin "14") (pinfunction "14_14") (pintype "passive"))
    )
    (net (code "118") (name "unconnected-(U7-Pad15)") (class "Default")
      (node (ref "U7") (pin "15") (pinfunction "15_15") (pintype "passive"))
    )
    (net (code "119") (name "unconnected-(U7-Pad16)") (class "Default")
      (node (ref "U7") (pin "16") (pinfunction "16_16") (pintype "passive"))
    )
    (net (code "120") (name "unconnected-(U7-Pad17)") (class "Default")
      (node (ref "U7") (pin "17") (pinfunction "17_17") (pintype "passive"))
    )
    (net (code "121") (name "unconnected-(U7-RESV-Pad19)") (class "Default")
      (node (ref "U7") (pin "19") (pinfunction "RESV_19") (pintype "passive"))
    )
    (net (code "122") (name "unconnected-(U7-RESV-Pad21)") (class "Default")
      (node (ref "U7") (pin "21") (pinfunction "RESV_21") (pintype "passive"))
    )
    (net (code "123") (name "unconnected-(USB2-ID-Pad4)") (class "Default")
      (node (ref "USB2") (pin "4") (pinfunction "ID_4") (pintype "passive"))
    )
  )
)
